# SCH_MuteMe-Arduino_2022-08-23.net
KiCad netlist of a schematic drawn in EasyEDA
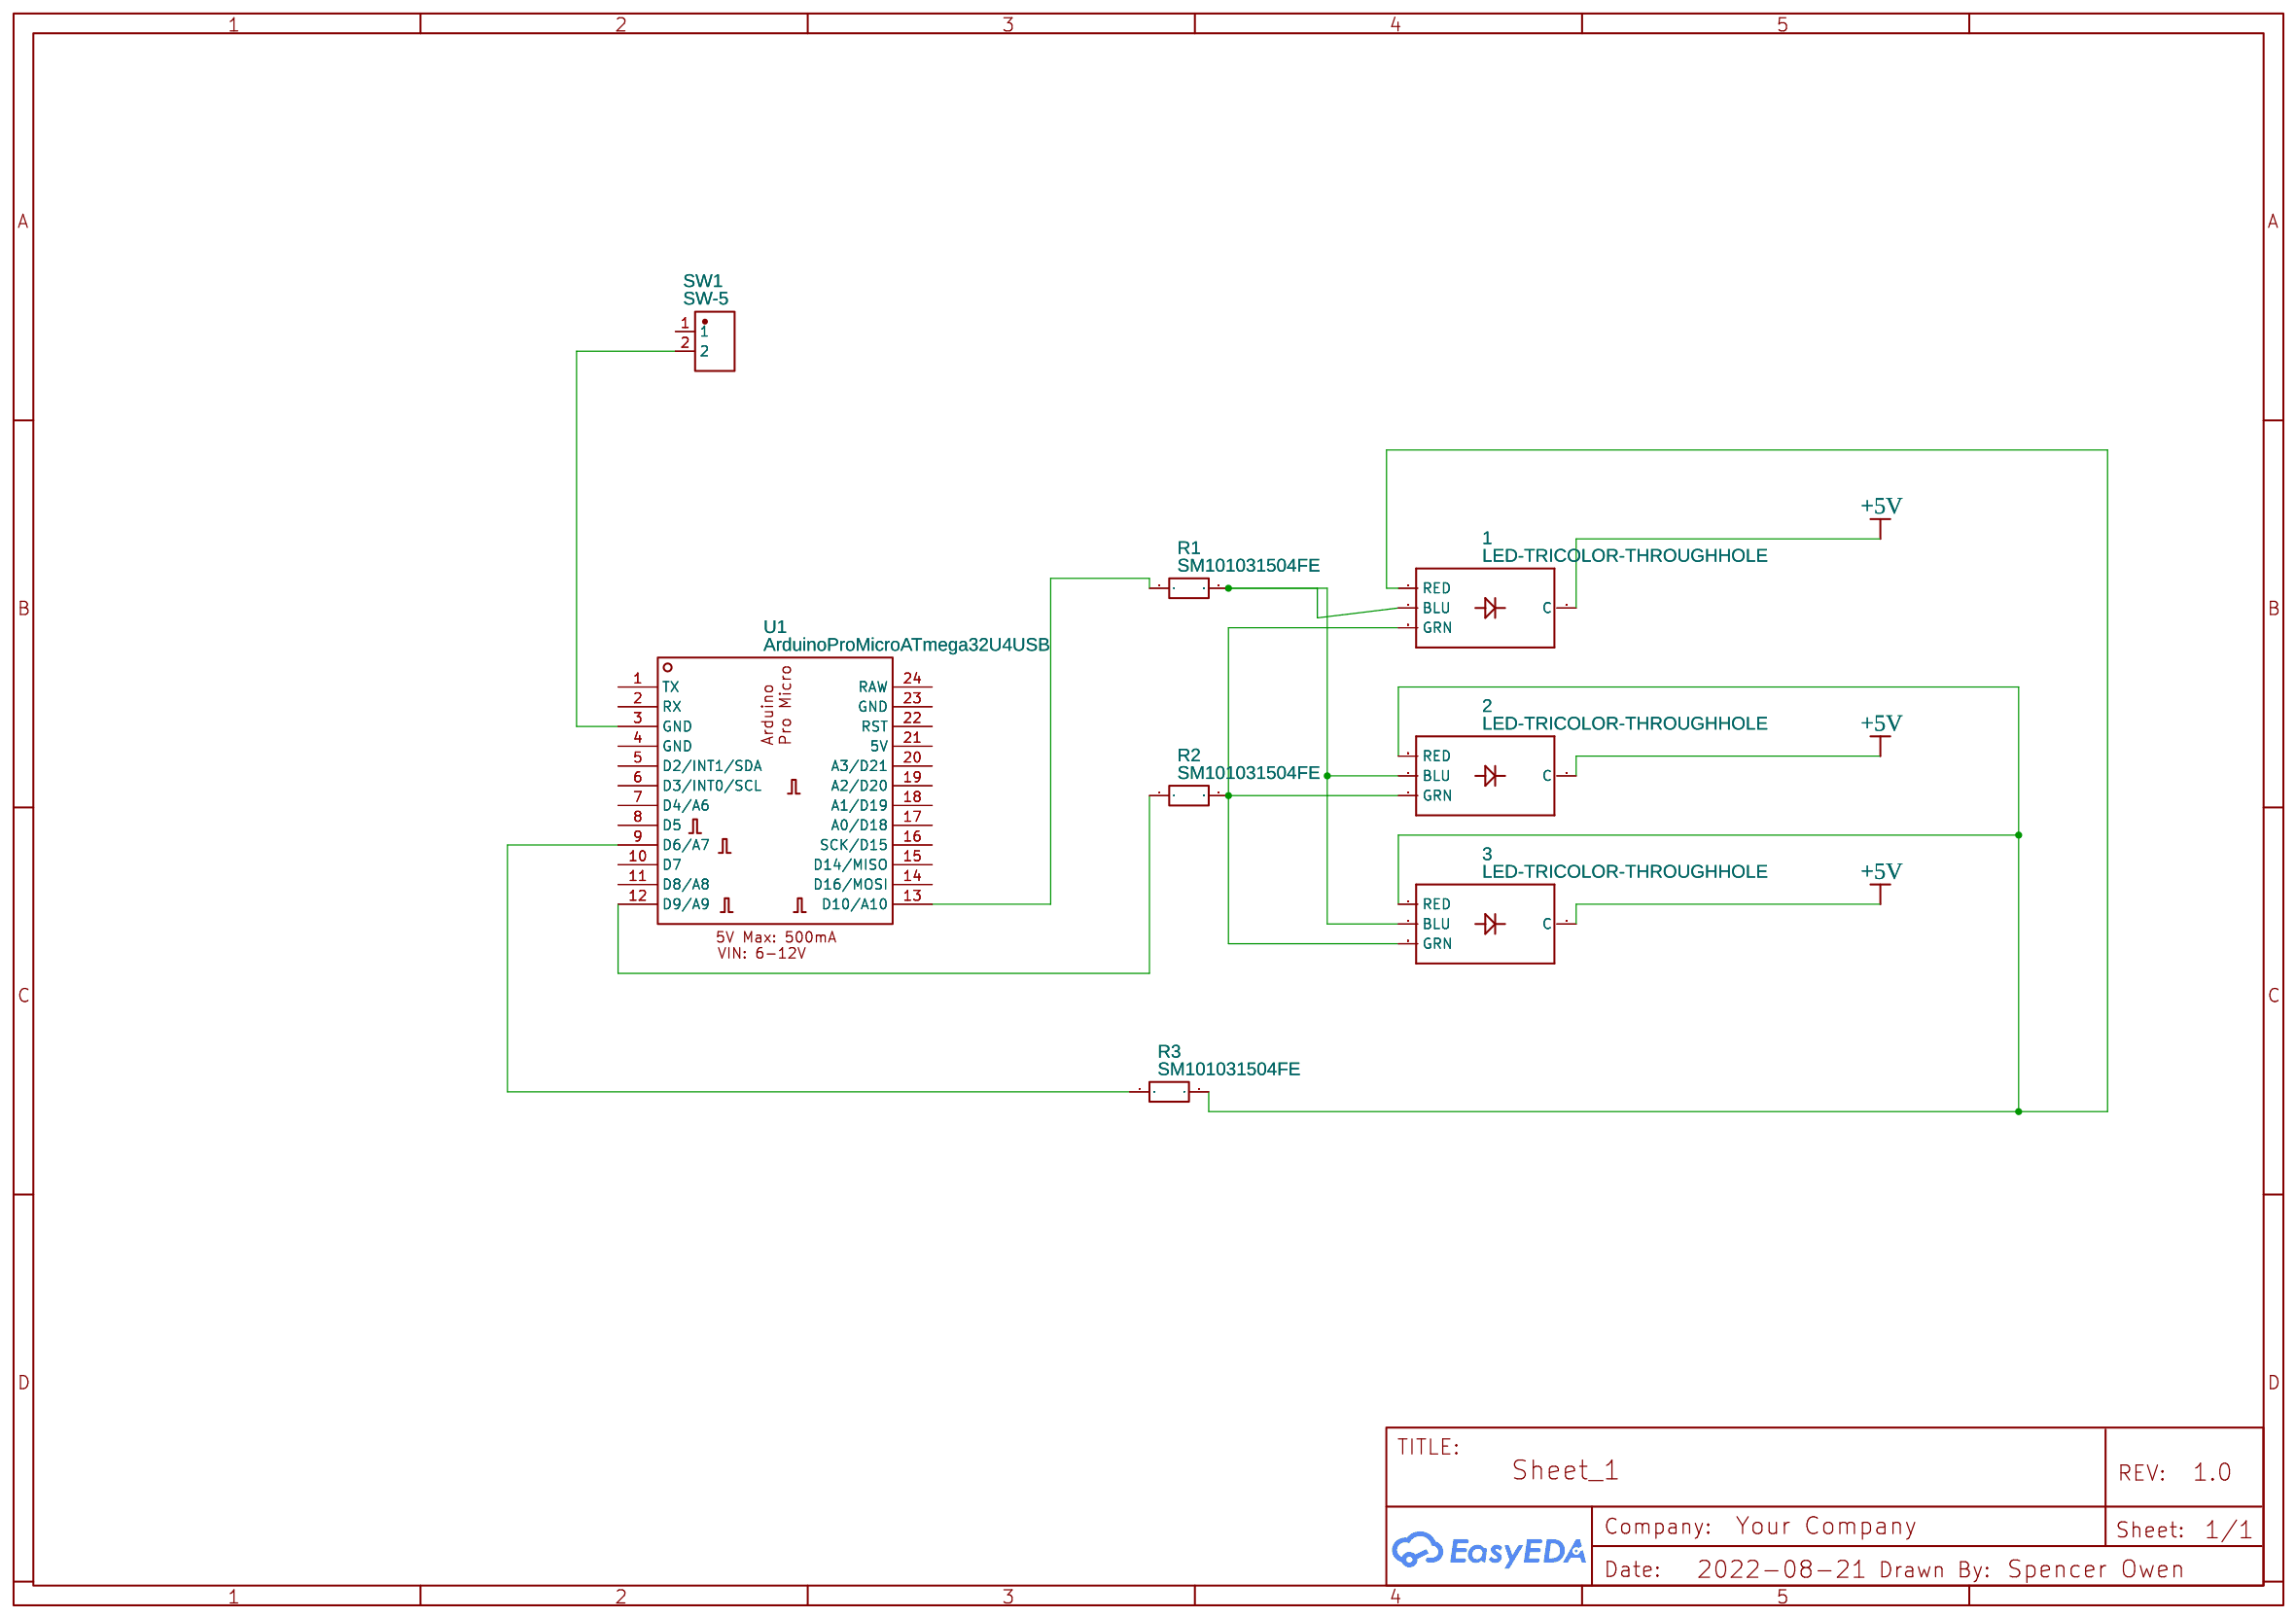
[diagram p0: schematic sheet]

(export (version "E")
  (design (tool "Eeschema 10.0.6"))
  (components
    (comp (ref "1") (value "LED-TRICOLOR-THROUGHHOLE") (libsource (lib "") (part "LED-TRICOLOR-THROUGHHOLE")))
    (comp (ref "2") (value "LED-TRICOLOR-THROUGHHOLE") (libsource (lib "") (part "LED-TRICOLOR-THROUGHHOLE")))
    (comp (ref "3") (value "LED-TRICOLOR-THROUGHHOLE") (libsource (lib "") (part "LED-TRICOLOR-THROUGHHOLE")))
    (comp (ref "R1")
      (value "SM101031504FE")
      (fields (field (name "BOM_Supplier Part") "C3577345"))
      (libsource (lib "") (part "SM101031504FE"))
    )
    (comp (ref "R2")
      (value "SM101031504FE")
      (fields (field (name "BOM_Supplier Part") "C3577345"))
      (libsource (lib "") (part "SM101031504FE"))
    )
    (comp (ref "R3")
      (value "SM101031504FE")
      (fields (field (name "BOM_Supplier Part") "C3577345"))
      (libsource (lib "") (part "SM101031504FE"))
    )
    (comp (ref "SW1")
      (value "SW-5")
      (fields (field (name "BOM_Supplier Part") "C9900019772"))
      (libsource (lib "") (part "SW-5"))
    )
    (comp (ref "U1")
      (value "ArduinoProMicroATmega32U4USB")
      (libsource (lib "") (part "ArduinoProMicroATmega32U4USB"))
    )
  )
  (nets
    (net (code "1") (name "+5V") (class "Default")
      (node (ref "1") (pin "GND") (pinfunction "C_GND") (pintype "bidirectional"))
      (node (ref "2") (pin "GND") (pinfunction "C_GND") (pintype "bidirectional"))
      (node (ref "3") (pin "GND") (pinfunction "C_GND") (pintype "bidirectional"))
    )
    (net (code "2") (name "Net-(1-PadBLU)") (class "Default")
      (node (ref "1") (pin "BLU") (pinfunction "BLU_BLU") (pintype "bidirectional"))
      (node (ref "2") (pin "BLU") (pinfunction "BLU_BLU") (pintype "bidirectional"))
      (node (ref "3") (pin "BLU") (pinfunction "BLU_BLU") (pintype "bidirectional"))
      (node (ref "R1") (pin "2") (pinfunction "2_2") (pintype "unspecified"))
    )
    (net (code "3") (name "Net-(1-PadGRN)") (class "Default")
      (node (ref "1") (pin "GRN") (pinfunction "GRN_GRN") (pintype "bidirectional"))
      (node (ref "2") (pin "GRN") (pinfunction "GRN_GRN") (pintype "bidirectional"))
      (node (ref "3") (pin "GRN") (pinfunction "GRN_GRN") (pintype "bidirectional"))
      (node (ref "R2") (pin "2") (pinfunction "2_2") (pintype "unspecified"))
    )
    (net (code "4") (name "Net-(1-PadRED)") (class "Default")
      (node (ref "1") (pin "RED") (pinfunction "RED_RED") (pintype "bidirectional"))
      (node (ref "2") (pin "RED") (pinfunction "RED_RED") (pintype "bidirectional"))
      (node (ref "3") (pin "RED") (pinfunction "RED_RED") (pintype "bidirectional"))
      (node (ref "R3") (pin "2") (pinfunction "2_2") (pintype "unspecified"))
    )
    (net (code "5") (name "Net-(SW1-Pad2)") (class "Default")
      (node (ref "SW1") (pin "2") (pinfunction "2_2") (pintype "unspecified"))
      (node (ref "U1") (pin "3") (pinfunction "GND_3") (pintype "unspecified"))
    )
    (net (code "6") (name "Net-(U1-D6{slash}A7)") (class "Default")
      (node (ref "R3") (pin "1") (pinfunction "1_1") (pintype "unspecified"))
      (node (ref "U1") (pin "9") (pinfunction "D6/A7_9") (pintype "unspecified"))
    )
    (net (code "7") (name "Net-(U1-D9{slash}A9)") (class "Default")
      (node (ref "R2") (pin "1") (pinfunction "1_1") (pintype "unspecified"))
      (node (ref "U1") (pin "12") (pinfunction "D9/A9_12") (pintype "unspecified"))
    )
    (net (code "8") (name "Net-(U1-D10{slash}A10)") (class "Default")
      (node (ref "R1") (pin "1") (pinfunction "1_1") (pintype "unspecified"))
      (node (ref "U1") (pin "13") (pinfunction "D10/A10_13") (pintype "unspecified"))
    )
    (net (code "9") (name "unconnected-(SW1-Pad1)") (class "Default")
      (node (ref "SW1") (pin "1") (pinfunction "1_1") (pintype "unspecified"))
    )
    (net (code "10") (name "unconnected-(U1-5V-Pad21)") (class "Default")
      (node (ref "U1") (pin "21") (pinfunction "5V_21") (pintype "unspecified"))
    )
    (net (code "11") (name "unconnected-(U1-A0{slash}D18-Pad17)") (class "Default")
      (node (ref "U1") (pin "17") (pinfunction "A0/D18_17") (pintype "unspecified"))
    )
    (net (code "12") (name "unconnected-(U1-A1{slash}D19-Pad18)") (class "Default")
      (node (ref "U1") (pin "18") (pinfunction "A1/D19_18") (pintype "unspecified"))
    )
    (net (code "13") (name "unconnected-(U1-A2{slash}D20-Pad19)") (class "Default")
      (node (ref "U1") (pin "19") (pinfunction "A2/D20_19") (pintype "unspecified"))
    )
    (net (code "14") (name "unconnected-(U1-A3{slash}D21-Pad20)") (class "Default")
      (node (ref "U1") (pin "20") (pinfunction "A3/D21_20") (pintype "unspecified"))
    )
    (net (code "15") (name "unconnected-(U1-D2{slash}INT1{slash}SDA-Pad5)") (class "Default")
      (node (ref "U1") (pin "5") (pinfunction "D2/INT1/SDA_5") (pintype "unspecified"))
    )
    (net (code "16") (name "unconnected-(U1-D3{slash}INT0{slash}SCL-Pad6)") (class "Default")
      (node (ref "U1") (pin "6") (pinfunction "D3/INT0/SCL_6") (pintype "unspecified"))
    )
    (net (code "17") (name "unconnected-(U1-D4{slash}A6-Pad7)") (class "Default")
      (node (ref "U1") (pin "7") (pinfunction "D4/A6_7") (pintype "unspecified"))
    )
    (net (code "18") (name "unconnected-(U1-D5-Pad8)") (class "Default")
      (node (ref "U1") (pin "8") (pinfunction "D5_8") (pintype "unspecified"))
    )
    (net (code "19") (name "unconnected-(U1-D7-Pad10)") (class "Default")
      (node (ref "U1") (pin "10") (pinfunction "D7_10") (pintype "unspecified"))
    )
    (net (code "20") (name "unconnected-(U1-D8{slash}A8-Pad11)") (class "Default")
      (node (ref "U1") (pin "11") (pinfunction "D8/A8_11") (pintype "unspecified"))
    )
    (net (code "21") (name "unconnected-(U1-D14{slash}MISO-Pad15)") (class "Default")
      (node (ref "U1") (pin "15") (pinfunction "D14/MISO_15") (pintype "unspecified"))
    )
    (net (code "22") (name "unconnected-(U1-D16{slash}MOSI-Pad14)") (class "Default")
      (node (ref "U1") (pin "14") (pinfunction "D16/MOSI_14") (pintype "unspecified"))
    )
    (net (code "23") (name "unconnected-(U1-GND-Pad4)") (class "Default")
      (node (ref "U1") (pin "4") (pinfunction "GND_4") (pintype "unspecified"))
    )
    (net (code "24") (name "unconnected-(U1-GND-Pad23)") (class "Default")
      (node (ref "U1") (pin "23") (pinfunction "GND_23") (pintype "unspecified"))
    )
    (net (code "25") (name "unconnected-(U1-RAW-Pad24)") (class "Default")
      (node (ref "U1") (pin "24") (pinfunction "RAW_24") (pintype "unspecified"))
    )
    (net (code "26") (name "unconnected-(U1-RST-Pad22)") (class "Default")
      (node (ref "U1") (pin "22") (pinfunction "RST_22") (pintype "unspecified"))
    )
    (net (code "27") (name "unconnected-(U1-RX-Pad2)") (class "Default")
      (node (ref "U1") (pin "2") (pinfunction "RX_2") (pintype "unspecified"))
    )
    (net (code "28") (name "unconnected-(U1-SCK{slash}D15-Pad16)") (class "Default")
      (node (ref "U1") (pin "16") (pinfunction "SCK/D15_16") (pintype "unspecified"))
    )
    (net (code "29") (name "unconnected-(U1-TX-Pad1)") (class "Default")
      (node (ref "U1") (pin "1") (pinfunction "TX_1") (pintype "unspecified"))
    )
  )
)
